# Spatial_Breakout.net
KiCad netlist of a schematic drawn in Altium Designer
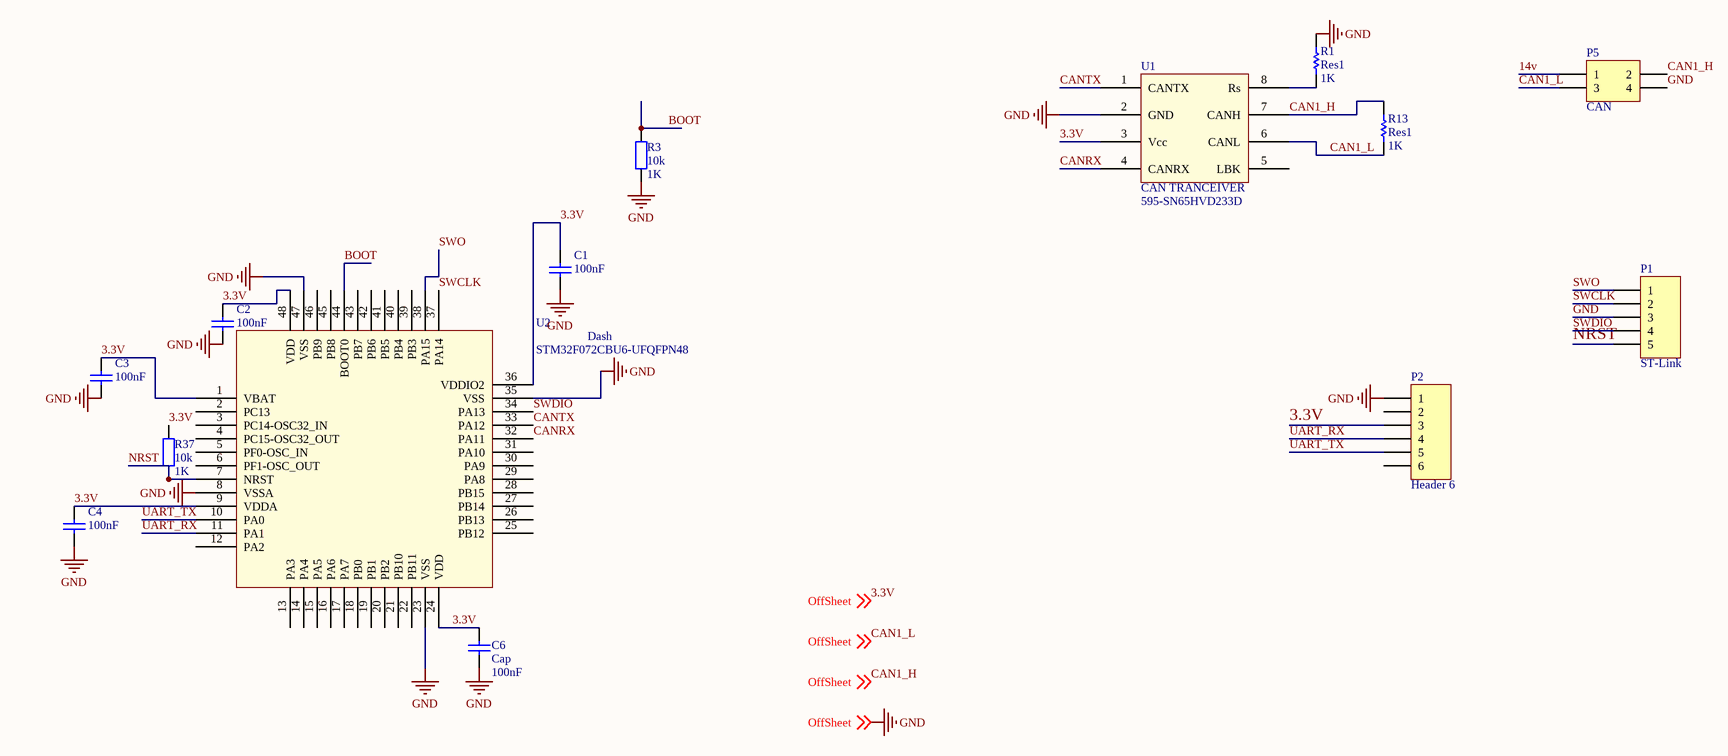
[diagram p0: Spatial Breakout.SchDoc]

(export (version "E")
  (design (tool "Eeschema 10.0.6"))
  (components
    (comp (ref "C1")
      (value "100nF")
      (footprint "R0805")
      (description "Capacitor (Semiconductor SIM Model)")
      (fields (field (name "PUBLISHER") "Altium Limited"))
      (libsource (lib "Miscellaneous Devices") (part "Cap Semi"))
    )
    (comp (ref "C2")
      (value "100nF")
      (footprint "R0805")
      (description "Capacitor (Semiconductor SIM Model)")
      (fields (field (name "PUBLISHER") "Altium Limited"))
      (libsource (lib "Miscellaneous Devices") (part "Cap Semi"))
    )
    (comp (ref "C3")
      (value "100nF")
      (footprint "R0805")
      (description "Capacitor (Semiconductor SIM Model)")
      (fields (field (name "PUBLISHER") "Altium Limited"))
      (libsource (lib "Miscellaneous Devices") (part "Cap Semi"))
    )
    (comp (ref "C4")
      (value "100nF")
      (footprint "R0805")
      (description "Capacitor (Semiconductor SIM Model)")
      (fields (field (name "PUBLISHER") "Altium Limited"))
      (libsource (lib "Miscellaneous Devices") (part "Cap Semi"))
    )
    (comp (ref "C6")
      (value "Cap")
      (footprint "R0805")
      (description "Capacitor")
      (fields (field (name "ALTIUM_VALUE") "100nF") (field (name "PUBLISHER") "Altium Limited"))
      (libsource (lib "Miscellaneous Devices") (part "Cap"))
    )
    (comp (ref "P1")
      (value "ST-Link")
      (footprint "SMD 5Wire - Small")
      (description "Header, 5-Pin")
      (fields (field (name "PUBLISHER") "Altium Limited"))
      (libsource (lib "Miscellaneous Connectors") (part "Header 5"))
    )
    (comp (ref "P2")
      (value "Header 6")
      (footprint "HDR1X6")
      (description "Header, 6-Pin")
      (fields (field (name "PUBLISHER") "Altium Limited"))
      (libsource (lib "Miscellaneous Connectors") (part "Header 6"))
    )
    (comp (ref "P5")
      (value "CAN")
      (footprint "SMD 4Wire")
      (description "Header, 2-Pin, Dual row, Right Angle")
      (fields (field (name "PUBLISHER") "Altium Limited"))
      (libsource (lib "Miscellaneous Connectors") (part "Header 2X2H"))
    )
    (comp (ref "R1")
      (value "Res1")
      (footprint "R0805")
      (description "Resistor")
      (fields (field (name "ALTIUM_VALUE") "1K") (field (name "PUBLISHER") "Altium Limited"))
      (libsource (lib "Miscellaneous Devices") (part "Res1"))
    )
    (comp (ref "R3")
      (value "10k")
      (footprint "R0805")
      (description "Resistor")
      (fields (field (name "ALTIUM_VALUE") "1K") (field (name "PUBLISHER") "Altium Limited"))
      (libsource (lib "Miscellaneous Devices") (part "Res2"))
    )
    (comp (ref "R13")
      (value "Res1")
      (footprint "R0805")
      (description "Resistor")
      (fields (field (name "ALTIUM_VALUE") "1K") (field (name "PUBLISHER") "Altium Limited"))
      (libsource (lib "Miscellaneous Devices") (part "Res1"))
    )
    (comp (ref "R37")
      (value "10k")
      (footprint "R0805")
      (description "Resistor")
      (fields (field (name "ALTIUM_VALUE") "1K") (field (name "PUBLISHER") "Altium Limited"))
      (libsource (lib "Miscellaneous Devices") (part "Res2"))
    )
    (comp (ref "U1")
      (value "CAN TRANCEIVER")
      (footprint "SOP8")
      (fields (field (name "SUPPLIER PART NUMBER 1") "595-SN65HVD233D"))
      (libsource (lib "Misc_ICs-1") (part "595-SN65HVD233"))
    )
    (comp (ref "U2")
      (value "Dash")
      (footprint "STM32F072CBU6 - No Heatsink")
      (description "PDM Mk21 MICRO")
      (fields
        (field (name "MANUFACTURER") "ST Microelectrics")
        (field (name "PART NUMBER") "STM32F072CBU6-UFQFPN48")
      )
      (libsource (lib "STM32_1") (part "STM32F072CBU6"))
    )
  )
  (nets
    (net (code "1") (name "/14v") (class "Default")
      (node (ref "P5") (pin "1") (pinfunction "1_1") (pintype "passive"))
    )
    (net (code "2") (name "/BOOT") (class "Default")
      (node (ref "R3") (pin "2") (pinfunction "2_2") (pintype "passive"))
      (node (ref "U2") (pin "44") (pinfunction "BOOT0_44") (pintype "passive"))
    )
    (net (code "3") (name "/CANRX") (class "Default")
      (node (ref "U1") (pin "4") (pinfunction "CANRX_4") (pintype "passive"))
      (node (ref "U2") (pin "32") (pinfunction "PA11_32") (pintype "passive"))
    )
    (net (code "4") (name "/CANTX") (class "Default")
      (node (ref "U1") (pin "1") (pinfunction "CANTX_1") (pintype "passive"))
      (node (ref "U2") (pin "33") (pinfunction "PA12_33") (pintype "passive"))
    )
    (net (code "5") (name "/NRST") (class "Default")
      (node (ref "P1") (pin "5") (pinfunction "5_5") (pintype "passive"))
      (node (ref "R37") (pin "1") (pinfunction "1_1") (pintype "passive"))
      (node (ref "U2") (pin "7") (pinfunction "NRST_7") (pintype "passive"))
    )
    (net (code "6") (name "/SWCLK") (class "Default")
      (node (ref "P1") (pin "2") (pinfunction "2_2") (pintype "passive"))
      (node (ref "U2") (pin "37") (pinfunction "PA14_37") (pintype "passive"))
    )
    (net (code "7") (name "/SWDIO") (class "Default")
      (node (ref "P1") (pin "4") (pinfunction "4_4") (pintype "passive"))
      (node (ref "U2") (pin "34") (pinfunction "PA13_34") (pintype "passive"))
    )
    (net (code "8") (name "/SWO") (class "Default")
      (node (ref "P1") (pin "1") (pinfunction "1_1") (pintype "passive"))
      (node (ref "U2") (pin "38") (pinfunction "PA15_38") (pintype "passive"))
    )
    (net (code "9") (name "/UART_RX") (class "Default")
      (node (ref "P2") (pin "4") (pinfunction "4_4") (pintype "passive"))
      (node (ref "U2") (pin "11") (pinfunction "PA1_11") (pintype "passive"))
    )
    (net (code "10") (name "/UART_TX") (class "Default")
      (node (ref "P2") (pin "5") (pinfunction "5_5") (pintype "passive"))
      (node (ref "U2") (pin "10") (pinfunction "PA0_10") (pintype "passive"))
    )
    (net (code "11") (name "GND") (class "Default")
      (node (ref "C1") (pin "1") (pinfunction "1_1") (pintype "passive"))
      (node (ref "C1") (pin "2") (pinfunction "2_2") (pintype "passive"))
      (node (ref "C2") (pin "1") (pinfunction "1_1") (pintype "passive"))
      (node (ref "C2") (pin "2") (pinfunction "2_2") (pintype "passive"))
      (node (ref "C3") (pin "1") (pinfunction "1_1") (pintype "passive"))
      (node (ref "C3") (pin "2") (pinfunction "2_2") (pintype "passive"))
      (node (ref "C4") (pin "1") (pinfunction "1_1") (pintype "passive"))
      (node (ref "C4") (pin "2") (pinfunction "2_2") (pintype "passive"))
      (node (ref "C6") (pin "1") (pinfunction "1_1") (pintype "passive"))
      (node (ref "C6") (pin "2") (pinfunction "2_2") (pintype "passive"))
      (node (ref "P1") (pin "3") (pinfunction "3_3") (pintype "passive"))
      (node (ref "P2") (pin "1") (pinfunction "1_1") (pintype "passive"))
      (node (ref "P2") (pin "3") (pinfunction "3_3") (pintype "passive"))
      (node (ref "P5") (pin "2") (pinfunction "2_2") (pintype "passive"))
      (node (ref "P5") (pin "3") (pinfunction "3_3") (pintype "passive"))
      (node (ref "P5") (pin "4") (pinfunction "4_4") (pintype "passive"))
      (node (ref "R1") (pin "2") (pinfunction "2_2") (pintype "passive"))
      (node (ref "R13") (pin "1") (pinfunction "1_1") (pintype "passive"))
      (node (ref "R13") (pin "2") (pinfunction "2_2") (pintype "passive"))
      (node (ref "R3") (pin "1") (pinfunction "1_1") (pintype "passive"))
      (node (ref "R37") (pin "2") (pinfunction "2_2") (pintype "passive"))
      (node (ref "U1") (pin "2") (pinfunction "GND_2") (pintype "passive"))
      (node (ref "U1") (pin "3") (pinfunction "Vcc_3") (pintype "passive"))
      (node (ref "U1") (pin "6") (pinfunction "CANL_6") (pintype "passive"))
      (node (ref "U1") (pin "7") (pinfunction "CANH_7") (pintype "passive"))
      (node (ref "U2") (pin "1") (pinfunction "VBAT_1") (pintype "passive"))
      (node (ref "U2") (pin "23") (pinfunction "VSS_23") (pintype "passive"))
      (node (ref "U2") (pin "24") (pinfunction "VDD_24") (pintype "passive"))
      (node (ref "U2") (pin "35") (pinfunction "VSS_35") (pintype "passive"))
      (node (ref "U2") (pin "36") (pinfunction "VDDIO2_36") (pintype "passive"))
      (node (ref "U2") (pin "47") (pinfunction "VSS_47") (pintype "passive"))
      (node (ref "U2") (pin "48") (pinfunction "VDD_48") (pintype "passive"))
      (node (ref "U2") (pin "8") (pinfunction "VSSA_8") (pintype "passive"))
      (node (ref "U2") (pin "9") (pinfunction "VDDA_9") (pintype "passive"))
    )
    (net (code "12") (name "Net-(U1-Rs)") (class "Default")
      (node (ref "R1") (pin "1") (pinfunction "1_1") (pintype "passive"))
      (node (ref "U1") (pin "8") (pinfunction "Rs_8") (pintype "passive"))
    )
    (net (code "13") (name "unconnected-(P2-Pad2)") (class "Default")
      (node (ref "P2") (pin "2") (pinfunction "2_2") (pintype "passive"))
    )
    (net (code "14") (name "unconnected-(P2-Pad6)") (class "Default")
      (node (ref "P2") (pin "6") (pinfunction "6_6") (pintype "passive"))
    )
    (net (code "15") (name "unconnected-(U1-LBK-Pad5)") (class "Default")
      (node (ref "U1") (pin "5") (pinfunction "LBK_5") (pintype "passive"))
    )
    (net (code "16") (name "unconnected-(U2-PA2-Pad12)") (class "Default")
      (node (ref "U2") (pin "12") (pinfunction "PA2_12") (pintype "passive"))
    )
    (net (code "17") (name "unconnected-(U2-PA3-Pad13)") (class "Default")
      (node (ref "U2") (pin "13") (pinfunction "PA3_13") (pintype "passive"))
    )
    (net (code "18") (name "unconnected-(U2-PA4-Pad14)") (class "Default")
      (node (ref "U2") (pin "14") (pinfunction "PA4_14") (pintype "passive"))
    )
    (net (code "19") (name "unconnected-(U2-PA5-Pad15)") (class "Default")
      (node (ref "U2") (pin "15") (pinfunction "PA5_15") (pintype "passive"))
    )
    (net (code "20") (name "unconnected-(U2-PA6-Pad16)") (class "Default")
      (node (ref "U2") (pin "16") (pinfunction "PA6_16") (pintype "passive"))
    )
    (net (code "21") (name "unconnected-(U2-PA7-Pad17)") (class "Default")
      (node (ref "U2") (pin "17") (pinfunction "PA7_17") (pintype "passive"))
    )
    (net (code "22") (name "unconnected-(U2-PA8-Pad29)") (class "Default")
      (node (ref "U2") (pin "29") (pinfunction "PA8_29") (pintype "passive"))
    )
    (net (code "23") (name "unconnected-(U2-PA9-Pad30)") (class "Default")
      (node (ref "U2") (pin "30") (pinfunction "PA9_30") (pintype "passive"))
    )
    (net (code "24") (name "unconnected-(U2-PA10-Pad31)") (class "Default")
      (node (ref "U2") (pin "31") (pinfunction "PA10_31") (pintype "passive"))
    )
    (net (code "25") (name "unconnected-(U2-PB0-Pad18)") (class "Default")
      (node (ref "U2") (pin "18") (pinfunction "PB0_18") (pintype "passive"))
    )
    (net (code "26") (name "unconnected-(U2-PB1-Pad19)") (class "Default")
      (node (ref "U2") (pin "19") (pinfunction "PB1_19") (pintype "passive"))
    )
    (net (code "27") (name "unconnected-(U2-PB2-Pad20)") (class "Default")
      (node (ref "U2") (pin "20") (pinfunction "PB2_20") (pintype "passive"))
    )
    (net (code "28") (name "unconnected-(U2-PB3-Pad39)") (class "Default")
      (node (ref "U2") (pin "39") (pinfunction "PB3_39") (pintype "passive"))
    )
    (net (code "29") (name "unconnected-(U2-PB4-Pad40)") (class "Default")
      (node (ref "U2") (pin "40") (pinfunction "PB4_40") (pintype "passive"))
    )
    (net (code "30") (name "unconnected-(U2-PB5-Pad41)") (class "Default")
      (node (ref "U2") (pin "41") (pinfunction "PB5_41") (pintype "passive"))
    )
    (net (code "31") (name "unconnected-(U2-PB6-Pad42)") (class "Default")
      (node (ref "U2") (pin "42") (pinfunction "PB6_42") (pintype "passive"))
    )
    (net (code "32") (name "unconnected-(U2-PB7-Pad43)") (class "Default")
      (node (ref "U2") (pin "43") (pinfunction "PB7_43") (pintype "passive"))
    )
    (net (code "33") (name "unconnected-(U2-PB8-Pad45)") (class "Default")
      (node (ref "U2") (pin "45") (pinfunction "PB8_45") (pintype "passive"))
    )
    (net (code "34") (name "unconnected-(U2-PB9-Pad46)") (class "Default")
      (node (ref "U2") (pin "46") (pinfunction "PB9_46") (pintype "passive"))
    )
    (net (code "35") (name "unconnected-(U2-PB10-Pad21)") (class "Default")
      (node (ref "U2") (pin "21") (pinfunction "PB10_21") (pintype "passive"))
    )
    (net (code "36") (name "unconnected-(U2-PB11-Pad22)") (class "Default")
      (node (ref "U2") (pin "22") (pinfunction "PB11_22") (pintype "passive"))
    )
    (net (code "37") (name "unconnected-(U2-PB12-Pad25)") (class "Default")
      (node (ref "U2") (pin "25") (pinfunction "PB12_25") (pintype "passive"))
    )
    (net (code "38") (name "unconnected-(U2-PB13-Pad26)") (class "Default")
      (node (ref "U2") (pin "26") (pinfunction "PB13_26") (pintype "passive"))
    )
    (net (code "39") (name "unconnected-(U2-PB14-Pad27)") (class "Default")
      (node (ref "U2") (pin "27") (pinfunction "PB14_27") (pintype "passive"))
    )
    (net (code "40") (name "unconnected-(U2-PB15-Pad28)") (class "Default")
      (node (ref "U2") (pin "28") (pinfunction "PB15_28") (pintype "passive"))
    )
    (net (code "41") (name "unconnected-(U2-PC13-Pad2)") (class "Default")
      (node (ref "U2") (pin "2") (pinfunction "PC13_2") (pintype "passive"))
    )
    (net (code "42") (name "unconnected-(U2-PC14-OSC32_IN-Pad3)") (class "Default")
      (node (ref "U2") (pin "3") (pinfunction "PC14-OSC32_IN_3") (pintype "passive"))
    )
    (net (code "43") (name "unconnected-(U2-PC15-OSC32_OUT-Pad4)") (class "Default")
      (node (ref "U2") (pin "4") (pinfunction "PC15-OSC32_OUT_4") (pintype "passive"))
    )
    (net (code "44") (name "unconnected-(U2-PF0-OSC_IN-Pad5)") (class "Default")
      (node (ref "U2") (pin "5") (pinfunction "PF0-OSC_IN_5") (pintype "passive"))
    )
    (net (code "45") (name "unconnected-(U2-PF1-OSC_OUT-Pad6)") (class "Default")
      (node (ref "U2") (pin "6") (pinfunction "PF1-OSC_OUT_6") (pintype "passive"))
    )
  )
)
